# Sheet1.net
KiCad netlist of a schematic drawn in Altium Designer
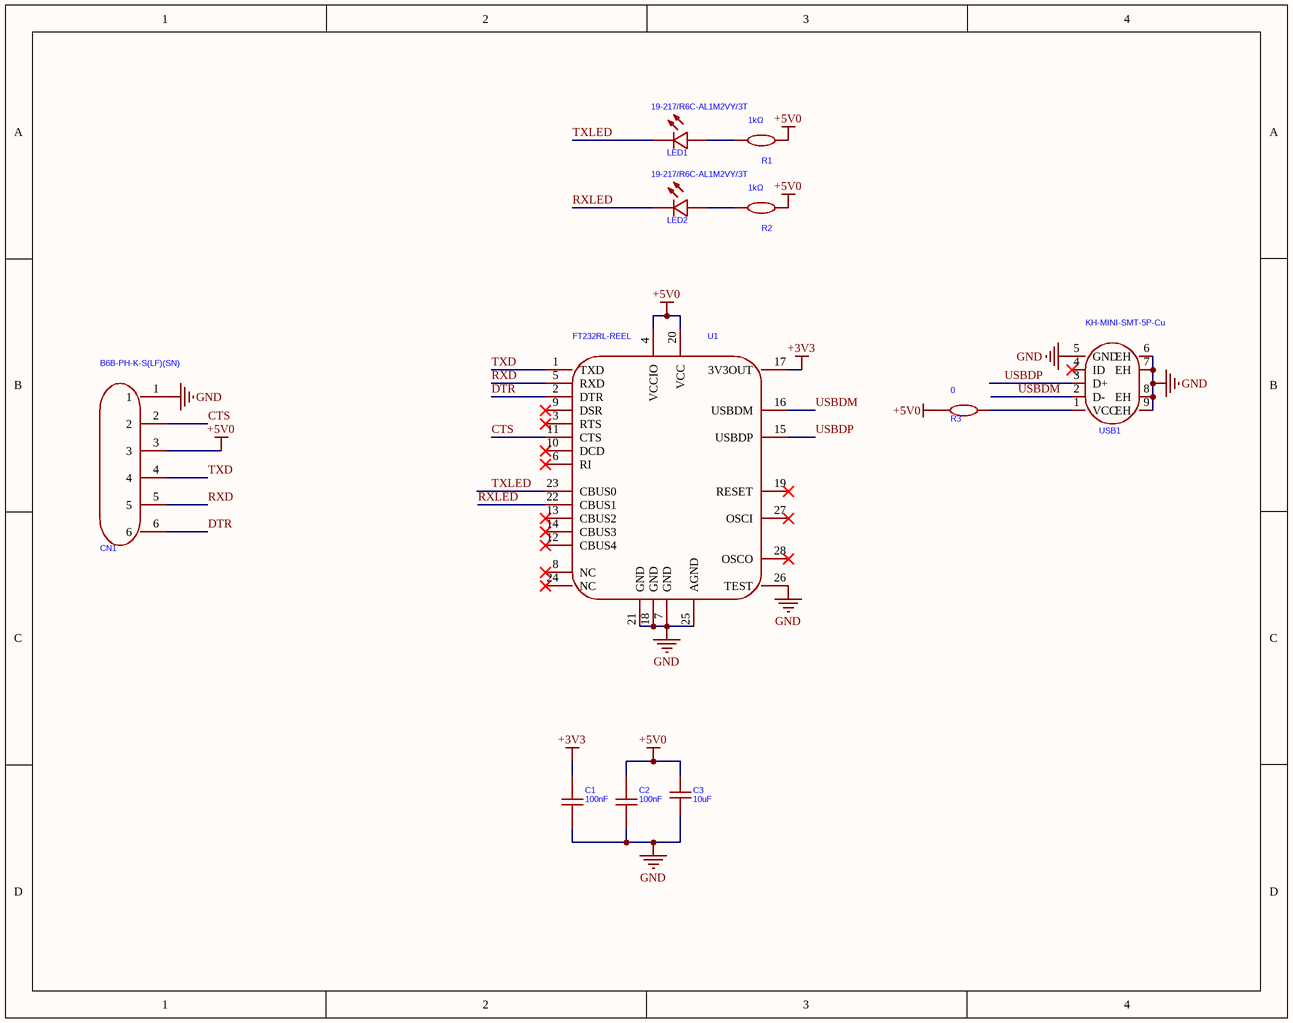
[diagram p0: Sheet1.SchDoc]

(export (version "E")
  (design (tool "Eeschema 10.0.6"))
  (components
    (comp (ref "C1")
      (value "100nF")
      (footprint "C0603")
      (fields
        (field (name "MANUFACTURER") "YAGEO(国巨)")
        (field (name "MANUFACTURER PART") "CC0603KRX7R9BB104")
        (field (name "TOLERANCE") "±10%")
      )
      (libsource (lib "Schlib1") (part "CC0603KRX7R9BB104"))
    )
    (comp (ref "C2")
      (value "100nF")
      (footprint "C0603")
      (fields
        (field (name "MANUFACTURER") "YAGEO(国巨)")
        (field (name "MANUFACTURER PART") "CC0603KRX7R9BB104")
        (field (name "TOLERANCE") "±10%")
      )
      (libsource (lib "Schlib1") (part "CC0603KRX7R9BB104"))
    )
    (comp (ref "C3")
      (value "10uF")
      (footprint "C1206")
      (fields
        (field (name "MANUFACTURER") "SAMSUNG(三星)")
        (field (name "MANUFACTURER PART") "CL31A106KBHNNNE")
        (field (name "TOLERANCE") "±10%")
      )
      (libsource (lib "Schlib1") (part "CL31A106KBHNNNE"))
    )
    (comp (ref "CN1")
      (value "B6B-PH-K-S(LF)(SN)")
      (footprint "CONN-TH_B6B-PH-K-S")
      (fields (field (name "MANUFACTURER") "JST"))
      (libsource (lib "Schlib1") (part "B6B-PH-K-S(LF)(SN)_C131342"))
    )
    (comp (ref "LED1")
      (value "19-217/R6C-AL1M2VY/3T")
      (footprint "LED0603-RD")
      (fields (field (name "MANUFACTURER") "EVERLIGHT(亿光)"))
      (libsource (lib "Schlib1") (part "19-217/R6C-AL1M2VY/3T"))
    )
    (comp (ref "LED2")
      (value "19-217/R6C-AL1M2VY/3T")
      (footprint "LED0603-RD")
      (fields (field (name "MANUFACTURER") "EVERLIGHT(亿光)"))
      (libsource (lib "Schlib1") (part "19-217/R6C-AL1M2VY/3T"))
    )
    (comp (ref "R1")
      (value "1kΩ")
      (footprint "R0603")
      (fields
        (field (name "MANUFACTURER") "YAGEO(国巨)")
        (field (name "MANUFACTURER PART") "RC0603FR-071KL")
        (field (name "TOLERANCE") "±1%")
      )
      (libsource (lib "Schlib1") (part "RC0603FR-071KL"))
    )
    (comp (ref "R2")
      (value "1kΩ")
      (footprint "R0603")
      (fields
        (field (name "MANUFACTURER") "YAGEO(国巨)")
        (field (name "MANUFACTURER PART") "RC0603FR-071KL")
        (field (name "TOLERANCE") "±1%")
      )
      (libsource (lib "Schlib1") (part "RC0603FR-071KL"))
    )
    (comp (ref "R3")
      (value "0")
      (footprint "R0603")
      (fields
        (field (name "MANUFACTURER") "YAGEO(国巨)")
        (field (name "MANUFACTURER PART") "RC0603FR-071KL")
        (field (name "TOLERANCE") "±1%")
      )
      (libsource (lib "Schlib1") (part "RC0603FR-071KL"))
    )
    (comp (ref "U1")
      (value "FT232RL-REEL")
      (footprint "SSOP-28_L10.2-W5.3-P0.65-LS7.8-BL")
      (fields (field (name "MANUFACTURER") "FTDI(飞特帝亚)"))
      (libsource (lib "Schlib1") (part "FT232RL-REEL"))
    )
    (comp (ref "USB1")
      (value "KH-MINI-SMT-5P-Cu")
      (footprint "MINI-USB-SMD_KH-MINI-SMT-5P-CU")
      (fields (field (name "MANUFACTURER") "kinghelm(金航标)"))
      (libsource (lib "Schlib1") (part "KH-MINI-SMT-5P-Cu"))
    )
  )
  (nets
    (net (code "1") (name "+3V3") (class "Default")
      (node (ref "C1") (pin "2") (pinfunction "2_2") (pintype "passive"))
      (node (ref "U1") (pin "17") (pinfunction "3V3OUT_17") (pintype "passive"))
    )
    (net (code "2") (name "+5V0") (class "Default")
      (node (ref "C2") (pin "2") (pinfunction "2_2") (pintype "passive"))
      (node (ref "C3") (pin "2") (pinfunction "2_2") (pintype "passive"))
      (node (ref "CN1") (pin "3") (pinfunction "3_3") (pintype "passive"))
      (node (ref "R1") (pin "2") (pinfunction "2_2") (pintype "passive"))
      (node (ref "R2") (pin "2") (pinfunction "2_2") (pintype "passive"))
      (node (ref "R3") (pin "1") (pinfunction "1_1") (pintype "passive"))
      (node (ref "U1") (pin "20") (pinfunction "VCC_20") (pintype "passive"))
      (node (ref "U1") (pin "4") (pinfunction "VCCIO_4") (pintype "passive"))
    )
    (net (code "3") (name "/CTS") (class "Default")
      (node (ref "CN1") (pin "2") (pinfunction "2_2") (pintype "passive"))
      (node (ref "U1") (pin "11") (pinfunction "CTS_11") (pintype "passive"))
    )
    (net (code "4") (name "/DTR") (class "Default")
      (node (ref "CN1") (pin "6") (pinfunction "6_6") (pintype "passive"))
      (node (ref "U1") (pin "2") (pinfunction "DTR_2") (pintype "passive"))
    )
    (net (code "5") (name "/RXD") (class "Default")
      (node (ref "CN1") (pin "5") (pinfunction "5_5") (pintype "passive"))
      (node (ref "U1") (pin "5") (pinfunction "RXD_5") (pintype "passive"))
    )
    (net (code "6") (name "/RXLED") (class "Default")
      (node (ref "LED2") (pin "1") (pinfunction "C_1") (pintype "passive"))
      (node (ref "U1") (pin "22") (pinfunction "CBUS1_22") (pintype "passive"))
    )
    (net (code "7") (name "/TXD") (class "Default")
      (node (ref "CN1") (pin "4") (pinfunction "4_4") (pintype "passive"))
      (node (ref "U1") (pin "1") (pinfunction "TXD_1") (pintype "passive"))
    )
    (net (code "8") (name "/TXLED") (class "Default")
      (node (ref "LED1") (pin "1") (pinfunction "C_1") (pintype "passive"))
      (node (ref "U1") (pin "23") (pinfunction "CBUS0_23") (pintype "passive"))
    )
    (net (code "9") (name "/USBDM") (class "Default")
      (node (ref "U1") (pin "16") (pinfunction "USBDM_16") (pintype "passive"))
      (node (ref "USB1") (pin "2") (pinfunction "D-_2") (pintype "passive"))
    )
    (net (code "10") (name "/USBDP") (class "Default")
      (node (ref "U1") (pin "15") (pinfunction "USBDP_15") (pintype "passive"))
      (node (ref "USB1") (pin "3") (pinfunction "D+_3") (pintype "passive"))
    )
    (net (code "11") (name "GND") (class "Default")
      (node (ref "C1") (pin "1") (pinfunction "1_1") (pintype "passive"))
      (node (ref "C2") (pin "1") (pinfunction "1_1") (pintype "passive"))
      (node (ref "C3") (pin "1") (pinfunction "1_1") (pintype "passive"))
      (node (ref "CN1") (pin "1") (pinfunction "1_1") (pintype "passive"))
      (node (ref "U1") (pin "18") (pinfunction "GND_18") (pintype "passive"))
      (node (ref "U1") (pin "21") (pinfunction "GND_21") (pintype "passive"))
      (node (ref "U1") (pin "25") (pinfunction "AGND_25") (pintype "passive"))
      (node (ref "U1") (pin "26") (pinfunction "TEST_26") (pintype "passive"))
      (node (ref "U1") (pin "7") (pinfunction "GND_7") (pintype "passive"))
      (node (ref "USB1") (pin "5") (pinfunction "GND_5") (pintype "passive"))
      (node (ref "USB1") (pin "6") (pinfunction "EH_6") (pintype "passive"))
      (node (ref "USB1") (pin "7") (pinfunction "EH_7") (pintype "passive"))
      (node (ref "USB1") (pin "8") (pinfunction "EH_8") (pintype "passive"))
      (node (ref "USB1") (pin "9") (pinfunction "EH_9") (pintype "passive"))
    )
    (net (code "12") (name "Net-(LED1-A)") (class "Default")
      (node (ref "LED1") (pin "2") (pinfunction "A_2") (pintype "passive"))
      (node (ref "R1") (pin "1") (pinfunction "1_1") (pintype "passive"))
    )
    (net (code "13") (name "Net-(LED2-A)") (class "Default")
      (node (ref "LED2") (pin "2") (pinfunction "A_2") (pintype "passive"))
      (node (ref "R2") (pin "1") (pinfunction "1_1") (pintype "passive"))
    )
    (net (code "14") (name "Net-(USB1-VCC)") (class "Default")
      (node (ref "R3") (pin "2") (pinfunction "2_2") (pintype "passive"))
      (node (ref "USB1") (pin "1") (pinfunction "VCC_1") (pintype "passive"))
    )
    (net (code "15") (name "unconnected-(U1-CBUS2-Pad13)") (class "Default")
      (node (ref "U1") (pin "13") (pinfunction "CBUS2_13") (pintype "passive+no_connect"))
    )
    (net (code "16") (name "unconnected-(U1-CBUS3-Pad14)") (class "Default")
      (node (ref "U1") (pin "14") (pinfunction "CBUS3_14") (pintype "passive+no_connect"))
    )
    (net (code "17") (name "unconnected-(U1-CBUS4-Pad12)") (class "Default")
      (node (ref "U1") (pin "12") (pinfunction "CBUS4_12") (pintype "passive+no_connect"))
    )
    (net (code "18") (name "unconnected-(U1-DCD-Pad10)") (class "Default")
      (node (ref "U1") (pin "10") (pinfunction "DCD_10") (pintype "passive+no_connect"))
    )
    (net (code "19") (name "unconnected-(U1-DSR-Pad9)") (class "Default")
      (node (ref "U1") (pin "9") (pinfunction "DSR_9") (pintype "passive+no_connect"))
    )
    (net (code "20") (name "unconnected-(U1-NC-Pad8)") (class "Default")
      (node (ref "U1") (pin "8") (pinfunction "NC_8") (pintype "passive+no_connect"))
    )
    (net (code "21") (name "unconnected-(U1-NC-Pad24)") (class "Default")
      (node (ref "U1") (pin "24") (pinfunction "NC_24") (pintype "passive+no_connect"))
    )
    (net (code "22") (name "unconnected-(U1-OSCI-Pad27)") (class "Default")
      (node (ref "U1") (pin "27") (pinfunction "OSCI_27") (pintype "passive+no_connect"))
    )
    (net (code "23") (name "unconnected-(U1-OSCO-Pad28)") (class "Default")
      (node (ref "U1") (pin "28") (pinfunction "OSCO_28") (pintype "passive+no_connect"))
    )
    (net (code "24") (name "unconnected-(U1-RESET-Pad19)") (class "Default")
      (node (ref "U1") (pin "19") (pinfunction "RESET_19") (pintype "passive+no_connect"))
    )
    (net (code "25") (name "unconnected-(U1-RI-Pad6)") (class "Default")
      (node (ref "U1") (pin "6") (pinfunction "RI_6") (pintype "passive+no_connect"))
    )
    (net (code "26") (name "unconnected-(U1-RTS-Pad3)") (class "Default")
      (node (ref "U1") (pin "3") (pinfunction "RTS_3") (pintype "passive+no_connect"))
    )
    (net (code "27") (name "unconnected-(USB1-ID-Pad4)") (class "Default")
      (node (ref "USB1") (pin "4") (pinfunction "ID_4") (pintype "passive+no_connect"))
    )
  )
)
